# HDMI_to_RGB.net
KiCad netlist of a schematic drawn in Altium Designer
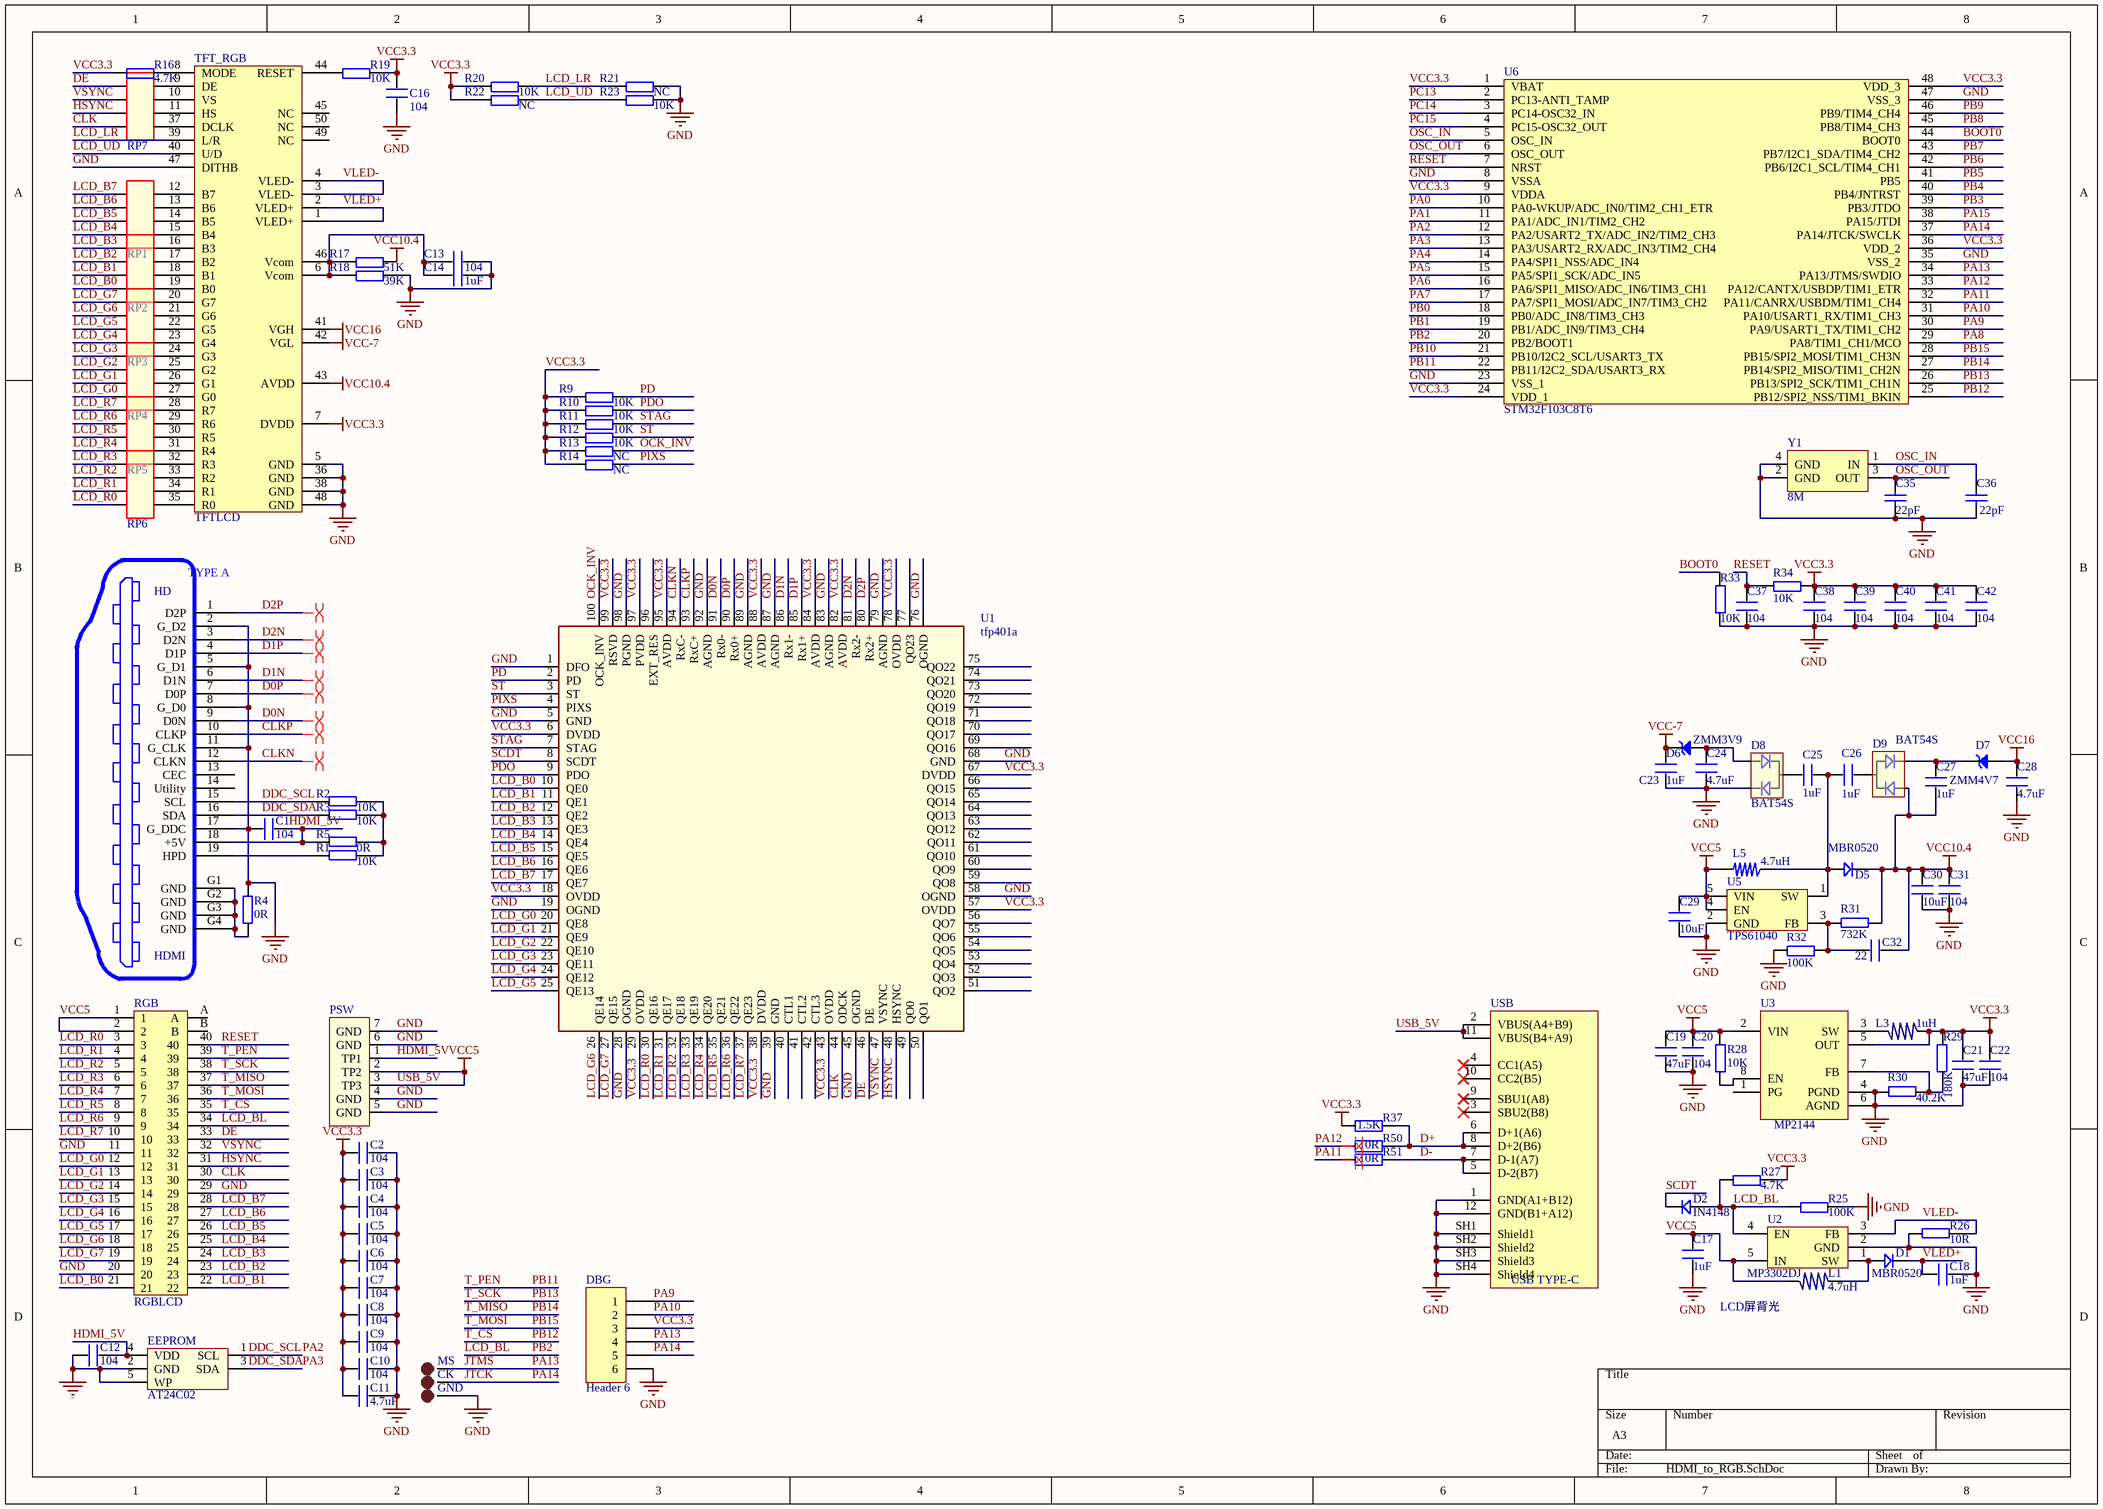
[diagram p0: HDMI_to_RGB.SchDoc]

(export (version "E")
  (design (tool "Eeschema 10.0.6"))
  (components
    (comp (ref "C1")
      (value "104")
      (footprint "C 0603_L")
      (libsource (lib "WarShip V3 STM32103封装库") (part "C"))
    )
    (comp (ref "C2")
      (value "104")
      (footprint "C 0603_L")
      (libsource (lib "WarShip V3 STM32103封装库") (part "C"))
    )
    (comp (ref "C3")
      (value "104")
      (footprint "C 0603_L")
      (libsource (lib "WarShip V3 STM32103封装库") (part "C"))
    )
    (comp (ref "C4")
      (value "104")
      (footprint "C 0603_L")
      (libsource (lib "WarShip V3 STM32103封装库") (part "C"))
    )
    (comp (ref "C5")
      (value "104")
      (footprint "C 0603_L")
      (libsource (lib "WarShip V3 STM32103封装库") (part "C"))
    )
    (comp (ref "C6")
      (value "104")
      (footprint "C 0603_L")
      (libsource (lib "WarShip V3 STM32103封装库") (part "C"))
    )
    (comp (ref "C7")
      (value "104")
      (footprint "C 0603_L")
      (libsource (lib "WarShip V3 STM32103封装库") (part "C"))
    )
    (comp (ref "C8")
      (value "104")
      (footprint "C 0603_L")
      (libsource (lib "WarShip V3 STM32103封装库") (part "C"))
    )
    (comp (ref "C9")
      (value "104")
      (footprint "C 0603_L")
      (libsource (lib "WarShip V3 STM32103封装库") (part "C"))
    )
    (comp (ref "C10")
      (value "104")
      (footprint "C 0603_L")
      (libsource (lib "WarShip V3 STM32103封装库") (part "C"))
    )
    (comp (ref "C11")
      (value "4.7uF")
      (footprint "C 0603_L")
      (libsource (lib "WarShip V3 STM32103封装库") (part "C"))
    )
    (comp (ref "C12")
      (value "104")
      (footprint "C 0603_L")
      (libsource (lib "WarShip V3 STM32103封装库") (part "C"))
    )
    (comp (ref "C13")
      (value "104")
      (footprint "C 0603_L")
      (libsource (lib "WarShip V3 STM32103封装库") (part "C"))
    )
    (comp (ref "C14")
      (value "1uF")
      (footprint "C 0603_L")
      (libsource (lib "WarShip V3 STM32103封装库") (part "C"))
    )
    (comp (ref "C16")
      (value "104")
      (footprint "C 0603_L")
      (libsource (lib "WarShip V3 STM32103封装库") (part "C"))
    )
    (comp (ref "C17") (value "1uF") (footprint "C 0603_L") (libsource (lib "阿波罗STM32F4&F7底板封装库") (part "C")))
    (comp (ref "C18") (value "1uF") (footprint "C 0603_L") (libsource (lib "阿波罗STM32F4&F7底板封装库") (part "C")))
    (comp (ref "C19")
      (value "47uF")
      (footprint "C 0805_L")
      (libsource (lib "WarShip V3 STM32103封装库") (part "C"))
    )
    (comp (ref "C20")
      (value "104")
      (footprint "C 0603_L")
      (libsource (lib "WarShip V3 STM32103封装库") (part "C"))
    )
    (comp (ref "C21")
      (value "47uF")
      (footprint "C 0805_L")
      (libsource (lib "WarShip V3 STM32103封装库") (part "C"))
    )
    (comp (ref "C22")
      (value "104")
      (footprint "C 0603_L")
      (libsource (lib "WarShip V3 STM32103封装库") (part "C"))
    )
    (comp (ref "C23") (value "1uF") (footprint "C 0603_L") (libsource (lib "ALIENTEK_COMPONENT") (part "C")))
    (comp (ref "C24")
      (value "4.7uF")
      (footprint "C 0603_L")
      (libsource (lib "ALIENTEK_COMPONENT") (part "C"))
    )
    (comp (ref "C25") (value "1uF") (footprint "C 0603_L") (libsource (lib "ALIENTEK_COMPONENT") (part "C")))
    (comp (ref "C26") (value "1uF") (footprint "C 0603_L") (libsource (lib "ALIENTEK_COMPONENT") (part "C")))
    (comp (ref "C27") (value "1uF") (footprint "C 0603_L") (libsource (lib "ALIENTEK_COMPONENT") (part "C")))
    (comp (ref "C28")
      (value "4.7uF")
      (footprint "C 0603_L")
      (libsource (lib "ALIENTEK_COMPONENT") (part "C"))
    )
    (comp (ref "C29") (value "10uF") (footprint "C 0603_L") (libsource (lib "ALIENTEK_COMPONENT") (part "C")))
    (comp (ref "C30") (value "10uF") (footprint "C 0603_L") (libsource (lib "ALIENTEK_COMPONENT") (part "C")))
    (comp (ref "C31") (value "104") (footprint "C 0603_L") (libsource (lib "ALIENTEK_COMPONENT") (part "C")))
    (comp (ref "C32") (value "22") (footprint "C 0603_L") (libsource (lib "ALIENTEK_COMPONENT") (part "C")))
    (comp (ref "C35") (value "22pF") (footprint "C 0603_L") (libsource (lib "L476") (part "CAP")))
    (comp (ref "C36") (value "22pF") (footprint "C 0603_L") (libsource (lib "L476") (part "CAP")))
    (comp (ref "C37")
      (value "104")
      (footprint "C 0603_L")
      (libsource (lib "WarShip V3 STM32103封装库") (part "C"))
    )
    (comp (ref "C38")
      (value "104")
      (footprint "C 0603_L")
      (libsource (lib "WarShip V3 STM32103封装库") (part "C"))
    )
    (comp (ref "C39")
      (value "104")
      (footprint "C 0603_L")
      (libsource (lib "WarShip V3 STM32103封装库") (part "C"))
    )
    (comp (ref "C40")
      (value "104")
      (footprint "C 0603_L")
      (libsource (lib "WarShip V3 STM32103封装库") (part "C"))
    )
    (comp (ref "C41")
      (value "104")
      (footprint "C 0603_L")
      (libsource (lib "WarShip V3 STM32103封装库") (part "C"))
    )
    (comp (ref "C42")
      (value "104")
      (footprint "C 0603_L")
      (libsource (lib "WarShip V3 STM32103封装库") (part "C"))
    )
    (comp (ref "CK")
      (value "TEST POINT")
      (footprint "TP-1.5")
      (description "测试点")
      (libsource (lib "STM32F767核心板封装库") (part "TEST-POINT"))
    )
    (comp (ref "D1")
      (value "MBR0520")
      (footprint "二极管-整流桥:SOD-123")
      (description "1N4148")
      (libsource (lib "ATK-4.3' TFTLCD电容触摸屏模块_V1.2") (part "D"))
    )
    (comp (ref "D2")
      (value "IN4148")
      (footprint "二极管-整流桥:SOD-123")
      (description "1N4148")
      (libsource (lib "ATK-4.3' TFTLCD电容触摸屏模块_V1.2") (part "D"))
    )
    (comp (ref "D5")
      (value "MBR0520")
      (footprint "二极管-整流桥:SOD-123")
      (description "1N4148")
      (libsource (lib "ALIENTEK_COMPONENT") (part "D"))
    )
    (comp (ref "D6")
      (value "ZMM3V9")
      (footprint "MINI_MELF (LL34)")
      (description "ZMM3V6")
      (libsource (lib "ALIENTEK_COMPONENT") (part "ZMM3V6"))
    )
    (comp (ref "D7")
      (value "ZMM4V7")
      (footprint "MINI_MELF (LL34)")
      (description "ZMM3V6")
      (libsource (lib "ALIENTEK_COMPONENT") (part "ZMM3V6"))
    )
    (comp (ref "D8")
      (value "BAT54S")
      (footprint "SOT23-3L")
      (description "双肖特基二极管")
      (libsource (lib "ALIENTEK_COMPONENT") (part "BAT54S"))
    )
    (comp (ref "D9")
      (value "BAT54S")
      (footprint "SOT23-3L")
      (description "双肖特基二极管")
      (libsource (lib "") (part "BAT54S_1"))
    )
    (comp (ref "DBG")
      (value "Header 6")
      (footprint "MX 1.25-LI-6P")
      (description "Header, 6-Pin")
      (fields (field (name "PUBLISHER") "Altium Limited"))
      (libsource (lib "Miscellaneous Connectors") (part "Header 6"))
    )
    (comp (ref "EEPROM")
      (value "AT24C02")
      (footprint "AT24C02")
      (libsource (lib "stm32f767igt6simple") (part "AT24C02"))
    )
    (comp (ref "GND")
      (value "TEST POINT")
      (footprint "TP-1.5")
      (description "测试点")
      (libsource (lib "STM32F767核心板封装库") (part "TEST-POINT"))
    )
    (comp (ref "HD")
      (value "HDMI")
      (footprint "HDMI_A")
      (libsource (lib "stm32f767igt6simple") (part "HDMI"))
    )
    (comp (ref "L1")
      (value "4.7uH")
      (footprint "NR4010")
      (libsource (lib "ATK-4.3' TFTLCD电容触摸屏模块_V1.2") (part "L"))
    )
    (comp (ref "L3") (value "1uH") (footprint "NR3015") (libsource (lib "MiniFly ") (part "L")))
    (comp (ref "L5")
      (value "4.7uH")
      (footprint "NR4010")
      (libsource (lib "ALIENTEK_COMPONENT") (part "L_SOP"))
    )
    (comp (ref "MS")
      (value "TEST POINT")
      (footprint "TP-1.5")
      (description "测试点")
      (libsource (lib "STM32F767核心板封装库") (part "TEST-POINT"))
    )
    (comp (ref "PSW") (value "SWITCH") (footprint "SWITCH") (libsource (lib "TP4056") (part "SWITCH")))
    (comp (ref "R1")
      (value "10K")
      (footprint "R 0603_L")
      (libsource (lib "WarShip V3 STM32103封装库") (part "R"))
    )
    (comp (ref "R2")
      (value "10K")
      (footprint "R 0603_L")
      (libsource (lib "WarShip V3 STM32103封装库") (part "R"))
    )
    (comp (ref "R3")
      (value "10K")
      (footprint "R 0603_L")
      (libsource (lib "WarShip V3 STM32103封装库") (part "R"))
    )
    (comp (ref "R4")
      (value "0R")
      (footprint "R 0603_L")
      (libsource (lib "WarShip V3 STM32103封装库") (part "R"))
    )
    (comp (ref "R5")
      (value "0R")
      (footprint "R 0603_L")
      (libsource (lib "WarShip V3 STM32103封装库") (part "R"))
    )
    (comp (ref "R9")
      (value "10K")
      (footprint "R 0603_L")
      (libsource (lib "WarShip V3 STM32103封装库") (part "R"))
    )
    (comp (ref "R10")
      (value "10K")
      (footprint "R 0603_L")
      (libsource (lib "WarShip V3 STM32103封装库") (part "R"))
    )
    (comp (ref "R11")
      (value "10K")
      (footprint "R 0603_L")
      (libsource (lib "WarShip V3 STM32103封装库") (part "R"))
    )
    (comp (ref "R12")
      (value "10K")
      (footprint "R 0603_L")
      (libsource (lib "WarShip V3 STM32103封装库") (part "R"))
    )
    (comp (ref "R13")
      (value "NC")
      (footprint "R 0603_L")
      (libsource (lib "WarShip V3 STM32103封装库") (part "R"))
    )
    (comp (ref "R14")
      (value "NC")
      (footprint "R 0603_L")
      (libsource (lib "WarShip V3 STM32103封装库") (part "R"))
    )
    (comp (ref "R16")
      (value "4.7K")
      (footprint "R 0603_L")
      (libsource (lib "WarShip V3 STM32103封装库") (part "R"))
    )
    (comp (ref "R17")
      (value "51K")
      (footprint "R 0603_L")
      (libsource (lib "WarShip V3 STM32103封装库") (part "R"))
    )
    (comp (ref "R18")
      (value "39K")
      (footprint "R 0603_L")
      (libsource (lib "WarShip V3 STM32103封装库") (part "R"))
    )
    (comp (ref "R19")
      (value "10K")
      (footprint "R 0603_L")
      (libsource (lib "WarShip V3 STM32103封装库") (part "R"))
    )
    (comp (ref "R20")
      (value "10K")
      (footprint "R 0603_L")
      (libsource (lib "WarShip V3 STM32103封装库") (part "R"))
    )
    (comp (ref "R21")
      (value "NC")
      (footprint "R 0603_L")
      (libsource (lib "WarShip V3 STM32103封装库") (part "R"))
    )
    (comp (ref "R22")
      (value "NC")
      (footprint "R 0603_L")
      (libsource (lib "WarShip V3 STM32103封装库") (part "R"))
    )
    (comp (ref "R23")
      (value "10K")
      (footprint "R 0603_L")
      (libsource (lib "WarShip V3 STM32103封装库") (part "R"))
    )
    (comp (ref "R25") (value "100K") (footprint "R 0603_L") (libsource (lib "阿波罗STM32F4&F7底板封装库") (part "R")))
    (comp (ref "R26") (value "10R") (footprint "R 0603_L") (libsource (lib "阿波罗STM32F4&F7底板封装库") (part "R")))
    (comp (ref "R27")
      (value "4.7K")
      (footprint "R 0603_L")
      (libsource (lib "WarShip V3 STM32103封装库") (part "R"))
    )
    (comp (ref "R28") (value "10K") (footprint "R 0603_L") (libsource (lib "阿波罗STM32F4&F7底板封装库") (part "R")))
    (comp (ref "R29") (value "180K") (footprint "R 0603_L") (libsource (lib "") (part "R_1")))
    (comp (ref "R30") (value "40.2K") (footprint "R 0603_L") (libsource (lib "") (part "R_1")))
    (comp (ref "R31") (value "732K") (footprint "R 0603_L") (libsource (lib "ALIENTEK_COMPONENT") (part "R")))
    (comp (ref "R32") (value "100K") (footprint "R 0603_L") (libsource (lib "ALIENTEK_COMPONENT") (part "R")))
    (comp (ref "R33")
      (value "10K")
      (footprint "R 0603_L")
      (libsource (lib "WarShip V3 STM32103封装库") (part "R"))
    )
    (comp (ref "R34")
      (value "10K")
      (footprint "R 0603_L")
      (libsource (lib "WarShip V3 STM32103封装库") (part "R"))
    )
    (comp (ref "R37")
      (value "1.5K")
      (footprint "R 0603_L")
      (description "贴片电阻")
      (fields (field (name "版权归属") "源创客"))
      (libsource (lib "电阻-电容-电感") (part "R"))
    )
    (comp (ref "R50")
      (value "10R")
      (footprint "R 0603_L")
      (description "贴片电阻")
      (fields (field (name "版权归属") "源创客"))
      (libsource (lib "电阻-电容-电感") (part "R"))
    )
    (comp (ref "R51")
      (value "10R")
      (footprint "R 0603_L")
      (description "贴片电阻")
      (fields (field (name "版权归属") "源创客"))
      (libsource (lib "电阻-电容-电感") (part "R"))
    )
    (comp (ref "RGB")
      (value "RGBLCD")
      (footprint "FPC0.5 2H-WS-40P")
      (description "FPC-40P-0.5mm")
      (libsource (lib "STM32F429核心板封装库") (part "FPC-40"))
    )
    (comp (ref "RP1")
      (value "33R")
      (footprint "P_pack")
      (libsource (lib "stm32f767igt6simple") (part "R_pack"))
    )
    (comp (ref "RP2")
      (value "33R")
      (footprint "P_pack")
      (libsource (lib "stm32f767igt6simple") (part "R_pack"))
    )
    (comp (ref "RP3")
      (value "33R")
      (footprint "P_pack")
      (libsource (lib "stm32f767igt6simple") (part "R_pack"))
    )
    (comp (ref "RP4")
      (value "33R")
      (footprint "P_pack")
      (libsource (lib "stm32f767igt6simple") (part "R_pack"))
    )
    (comp (ref "RP5")
      (value "33R")
      (footprint "P_pack")
      (libsource (lib "stm32f767igt6simple") (part "R_pack"))
    )
    (comp (ref "RP6")
      (value "33R")
      (footprint "P_pack")
      (libsource (lib "stm32f767igt6simple") (part "R_pack"))
    )
    (comp (ref "RP7")
      (value "33R")
      (footprint "P_pack")
      (libsource (lib "stm32f767igt6simple") (part "R_pack"))
    )
    (comp (ref "TFT_RGB")
      (value "TFTLCD")
      (footprint "FPC-TOP50")
      (description "7' TFTLCD")
      (libsource (lib "ATK-7016&7084 7寸RGB屏模块封装库") (part "AT070TN92"))
    )
    (comp (ref "U1")
      (value "tfp401a")
      (footprint "LQFP100")
      (libsource (lib "stm32f767igt6simple") (part "tfp401a"))
    )
    (comp (ref "U2")
      (value "MP3302DJ")
      (footprint "SOT:SOT23-5L")
      (description "LCD背光IC")
      (libsource (lib "ATK-4.3' TFTLCD电容触摸屏模块_V1.2") (part "MP3302"))
    )
    (comp (ref "U3") (value "MP2144") (footprint "SOT23-8L") (libsource (lib "LDO和DCDC") (part "MP2144")))
    (comp (ref "U5")
      (value "TPS61040")
      (footprint "SOT:SOT23-5L")
      (description "DC DC Step Up IC")
      (libsource (lib "ALIENTEK_COMPONENT") (part "TPS61040"))
    )
    (comp (ref "U6")
      (value "STM32F103C8T6")
      (footprint "LQFP48 7X7_L")
      (libsource (lib "Pandora_STM32L4_Board_V2.4") (part "U-STM32F103C8T6"))
    )
    (comp (ref "USB")
      (value "USB TypeC")
      (footprint "USB Type-C")
      (description "12P TypeC 母座")
      (libsource (lib "接口类") (part "USB Type-C"))
    )
    (comp (ref "Y1")
      (value "8M")
      (footprint "OSC 3225-4P")
      (description "4脚无源晶振")
      (fields (field (name "版权归属") "源创客"))
      (libsource (lib "保险丝-晶振") (part "XTAL-4P"))
    )
  )
  (nets
    (net (code "1") (name "/BOOT0") (class "Default")
      (node (ref "R33") (pin "2") (pintype "passive"))
      (node (ref "U6") (pin "44") (pinfunction "BOOT0_44") (pintype "passive"))
    )
    (net (code "2") (name "/CLK") (class "Default")
      (node (ref "RGB") (pin "30") (pinfunction "30_30") (pintype "passive"))
      (node (ref "RP7") (pin "7") (pintype "passive"))
      (node (ref "U1") (pin "44") (pinfunction "ODCK_44") (pintype "passive"))
    )
    (net (code "3") (name "/CLKN") (class "Default")
      (node (ref "HD") (pin "12") (pinfunction "CLKN_12") (pintype "passive"))
      (node (ref "U1") (pin "94") (pinfunction "RxC-_94") (pintype "passive"))
    )
    (net (code "4") (name "/CLKP") (class "Default")
      (node (ref "HD") (pin "10") (pinfunction "CLKP_10") (pintype "passive"))
      (node (ref "U1") (pin "93") (pinfunction "RxC+_93") (pintype "passive"))
    )
    (net (code "5") (name "/D+") (class "Default")
      (node (ref "R37") (pin "1") (pinfunction "1_1") (pintype "passive"))
      (node (ref "R50") (pin "1") (pinfunction "1_1") (pintype "passive"))
      (node (ref "USB") (pin "6") (pinfunction "D+1(A6)_6") (pintype "passive"))
      (node (ref "USB") (pin "8") (pinfunction "D+2(B6)_8") (pintype "passive"))
    )
    (net (code "6") (name "/D-") (class "Default")
      (node (ref "R51") (pin "1") (pinfunction "1_1") (pintype "passive"))
      (node (ref "USB") (pin "5") (pinfunction "D-2(B7)_5") (pintype "passive"))
      (node (ref "USB") (pin "7") (pinfunction "D-1(A7)_7") (pintype "passive"))
    )
    (net (code "7") (name "/D0N") (class "Default")
      (node (ref "HD") (pin "9") (pinfunction "D0N_9") (pintype "passive"))
      (node (ref "U1") (pin "91") (pinfunction "Rx0-_91") (pintype "passive"))
    )
    (net (code "8") (name "/D0P") (class "Default")
      (node (ref "HD") (pin "7") (pinfunction "D0P_7") (pintype "passive"))
      (node (ref "U1") (pin "90") (pinfunction "Rx0+_90") (pintype "passive"))
    )
    (net (code "9") (name "/D1N") (class "Default")
      (node (ref "HD") (pin "6") (pinfunction "D1N_6") (pintype "passive"))
      (node (ref "U1") (pin "86") (pinfunction "Rx1-_86") (pintype "passive"))
    )
    (net (code "10") (name "/D1P") (class "Default")
      (node (ref "HD") (pin "4") (pinfunction "D1P_4") (pintype "passive"))
      (node (ref "U1") (pin "85") (pinfunction "Rx1+_85") (pintype "passive"))
    )
    (net (code "11") (name "/D2N") (class "Default")
      (node (ref "HD") (pin "3") (pinfunction "D2N_3") (pintype "passive"))
      (node (ref "U1") (pin "81") (pinfunction "Rx2-_81") (pintype "passive"))
    )
    (net (code "12") (name "/D2P") (class "Default")
      (node (ref "HD") (pin "1") (pinfunction "D2P_1") (pintype "passive"))
      (node (ref "U1") (pin "80") (pinfunction "Rx2+_80") (pintype "passive"))
    )
    (net (code "13") (name "/DDC_SCL") (class "Default")
      (node (ref "EEPROM") (pin "1") (pinfunction "SCL_1") (pintype "passive"))
      (node (ref "HD") (pin "15") (pinfunction "SCL_15") (pintype "passive"))
      (node (ref "R2") (pin "2") (pintype "passive"))
      (node (ref "U6") (pin "12") (pinfunction "PA2/USART2_TX/ADC_IN2/TIM2_CH3_12") (pintype "passive"))
    )
    (net (code "14") (name "/DDC_SDA") (class "Default")
      (node (ref "EEPROM") (pin "3") (pinfunction "SDA_3") (pintype "passive"))
      (node (ref "HD") (pin "16") (pinfunction "SDA_16") (pintype "passive"))
      (node (ref "R3") (pin "2") (pintype "passive"))
      (node (ref "U6") (pin "13") (pinfunction "PA3/USART2_RX/ADC_IN3/TIM2_CH4_13") (pintype "passive"))
    )
    (net (code "15") (name "/DE") (class "Default")
      (node (ref "RGB") (pin "33") (pinfunction "33_33") (pintype "passive"))
      (node (ref "RP7") (pin "1") (pinfunction "1_1") (pintype "passive"))
      (node (ref "U1") (pin "46") (pinfunction "DE_46") (pintype "passive"))
    )
    (net (code "16") (name "/HDMI_5V") (class "Default")
      (node (ref "C1") (pin "1") (pintype "passive"))
      (node (ref "C12") (pin "2") (pintype "passive"))
      (node (ref "EEPROM") (pin "4") (pinfunction "VDD_4") (pintype "passive"))
      (node (ref "HD") (pin "18") (pinfunction "+5V_18") (pintype "passive"))
      (node (ref "PSW") (pin "1") (pinfunction "TP1_1") (pintype "passive"))
      (node (ref "R5") (pin "2") (pintype "passive"))
    )
    (net (code "17") (name "/HSYNC") (class "Default")
      (node (ref "RGB") (pin "31") (pinfunction "31_31") (pintype "passive"))
      (node (ref "RP7") (pin "5") (pintype "passive"))
      (node (ref "U1") (pin "48") (pinfunction "HSYNC_48") (pintype "passive"))
    )
    (net (code "18") (name "/JTCK") (class "Default")
      (node (ref "CK") (pin "1") (pinfunction "1_1") (pintype "passive"))
      (node (ref "DBG") (pin "5") (pinfunction "5_5") (pintype "passive"))
      (node (ref "U6") (pin "37") (pinfunction "PA14/JTCK/SWCLK_37") (pintype "passive"))
    )
    (net (code "19") (name "/JTMS") (class "Default")
      (node (ref "DBG") (pin "4") (pinfunction "4_4") (pintype "passive"))
      (node (ref "MS") (pin "1") (pinfunction "1_1") (pintype "passive"))
      (node (ref "U6") (pin "34") (pinfunction "PA13/JTMS/SWDIO_34") (pintype "passive"))
    )
    (net (code "20") (name "/LCD_B0") (class "Default")
      (node (ref "RGB") (pin "21") (pinfunction "21_21") (pintype "passive"))
      (node (ref "RP2") (pin "7") (pintype "passive"))
      (node (ref "U1") (pin "10") (pinfunction "QE0_10") (pintype "passive"))
    )
    (net (code "21") (name "/LCD_B1") (class "Default")
      (node (ref "RGB") (pin "22") (pinfunction "22_22") (pintype "passive"))
      (node (ref "RP2") (pin "5") (pintype "passive"))
      (node (ref "U1") (pin "11") (pinfunction "QE1_11") (pintype "passive"))
    )
    (net (code "22") (name "/LCD_B2") (class "Default")
      (node (ref "RGB") (pin "23") (pinfunction "23_23") (pintype "passive"))
      (node (ref "RP2") (pin "3") (pintype "passive"))
      (node (ref "U1") (pin "12") (pinfunction "QE2_12") (pintype "passive"))
    )
    (net (code "23") (name "/LCD_B3") (class "Default")
      (node (ref "RGB") (pin "24") (pinfunction "24_24") (pintype "passive"))
      (node (ref "RP2") (pin "1") (pinfunction "1_1") (pintype "passive"))
      (node (ref "U1") (pin "13") (pinfunction "QE3_13") (pintype "passive"))
    )
    (net (code "24") (name "/LCD_B4") (class "Default")
      (node (ref "RGB") (pin "25") (pinfunction "25_25") (pintype "passive"))
      (node (ref "RP1") (pin "7") (pintype "passive"))
      (node (ref "U1") (pin "14") (pinfunction "QE4_14") (pintype "passive"))
    )
    (net (code "25") (name "/LCD_B5") (class "Default")
      (node (ref "RGB") (pin "26") (pinfunction "26_26") (pintype "passive"))
      (node (ref "RP1") (pin "5") (pintype "passive"))
      (node (ref "U1") (pin "15") (pinfunction "QE5_15") (pintype "passive"))
    )
    (net (code "26") (name "/LCD_B6") (class "Default")
      (node (ref "RGB") (pin "27") (pinfunction "27_27") (pintype "passive"))
      (node (ref "RP1") (pin "3") (pintype "passive"))
      (node (ref "U1") (pin "16") (pinfunction "QE6_16") (pintype "passive"))
    )
    (net (code "27") (name "/LCD_B7") (class "Default")
      (node (ref "RGB") (pin "28") (pinfunction "28_28") (pintype "passive"))
      (node (ref "RP1") (pin "1") (pinfunction "1_1") (pintype "passive"))
      (node (ref "U1") (pin "17") (pinfunction "QE7_17") (pintype "passive"))
    )
    (net (code "28") (name "/LCD_BL") (class "Default")
      (node (ref "D2") (pin "1") (pintype "passive"))
      (node (ref "R25") (pin "1") (pintype "passive"))
      (node (ref "R27") (pin "1") (pintype "passive"))
      (node (ref "RGB") (pin "34") (pinfunction "34_34") (pintype "passive"))
      (node (ref "U2") (pin "4") (pinfunction "EN_4") (pintype "passive"))
      (node (ref "U6") (pin "20") (pinfunction "PB2/BOOT1_20") (pintype "passive"))
    )
    (net (code "29") (name "/LCD_G0") (class "Default")
      (node (ref "RGB") (pin "12") (pinfunction "12_12") (pintype "passive"))
      (node (ref "RP4") (pin "7") (pintype "passive"))
      (node (ref "U1") (pin "20") (pinfunction "QE8_20") (pintype "passive"))
    )
    (net (code "30") (name "/LCD_G1") (class "Default")
      (node (ref "RGB") (pin "13") (pinfunction "13_13") (pintype "passive"))
      (node (ref "RP4") (pin "5") (pintype "passive"))
      (node (ref "U1") (pin "21") (pinfunction "QE9_21") (pintype "passive"))
    )
    (net (code "31") (name "/LCD_G2") (class "Default")
      (node (ref "RGB") (pin "14") (pinfunction "14_14") (pintype "passive"))
      (node (ref "RP4") (pin "3") (pintype "passive"))
      (node (ref "U1") (pin "22") (pinfunction "QE10_22") (pintype "passive"))
    )
    (net (code "32") (name "/LCD_G3") (class "Default")
      (node (ref "RGB") (pin "15") (pinfunction "15_15") (pintype "passive"))
      (node (ref "RP4") (pin "1") (pinfunction "1_1") (pintype "passive"))
      (node (ref "U1") (pin "23") (pinfunction "QE11_23") (pintype "passive"))
    )
    (net (code "33") (name "/LCD_G4") (class "Default")
      (node (ref "RGB") (pin "16") (pinfunction "16_16") (pintype "passive"))
      (node (ref "RP3") (pin "7") (pintype "passive"))
      (node (ref "U1") (pin "24") (pinfunction "QE12_24") (pintype "passive"))
    )
    (net (code "34") (name "/LCD_G5") (class "Default")
      (node (ref "RGB") (pin "17") (pinfunction "17_17") (pintype "passive"))
      (node (ref "RP3") (pin "5") (pintype "passive"))
      (node (ref "U1") (pin "25") (pinfunction "QE13_25") (pintype "passive"))
    )
    (net (code "35") (name "/LCD_G6") (class "Default")
      (node (ref "RGB") (pin "18") (pinfunction "18_18") (pintype "passive"))
      (node (ref "RP3") (pin "3") (pintype "passive"))
      (node (ref "U1") (pin "26") (pinfunction "QE14_26") (pintype "passive"))
    )
    (net (code "36") (name "/LCD_G7") (class "Default")
      (node (ref "RGB") (pin "19") (pinfunction "19_19") (pintype "passive"))
      (node (ref "RP3") (pin "1") (pinfunction "1_1") (pintype "passive"))
      (node (ref "U1") (pin "27") (pinfunction "QE15_27") (pintype "passive"))
    )
    (net (code "37") (name "/LCD_LR") (class "Default")
      (node (ref "R20") (pin "2") (pintype "passive"))
      (node (ref "R21") (pin "1") (pintype "passive"))
      (node (ref "TFT_RGB") (pin "39") (pinfunction "L/R_39") (pintype "passive"))
    )
    (net (code "38") (name "/LCD_R0") (class "Default")
      (node (ref "RGB") (pin "3") (pinfunction "3_3") (pintype "passive"))
      (node (ref "RP6") (pin "7") (pintype "passive"))
      (node (ref "U1") (pin "30") (pinfunction "QE16_30") (pintype "passive"))
    )
    (net (code "39") (name "/LCD_R1") (class "Default")
      (node (ref "RGB") (pin "4") (pinfunction "4_4") (pintype "passive"))
      (node (ref "RP6") (pin "5") (pintype "passive"))
      (node (ref "U1") (pin "31") (pinfunction "QE17_31") (pintype "passive"))
    )
    (net (code "40") (name "/LCD_R2") (class "Default")
      (node (ref "RGB") (pin "5") (pinfunction "5_5") (pintype "passive"))
      (node (ref "RP6") (pin "3") (pintype "passive"))
      (node (ref "U1") (pin "32") (pinfunction "QE18_32") (pintype "passive"))
    )
    (net (code "41") (name "/LCD_R3") (class "Default")
      (node (ref "RGB") (pin "6") (pinfunction "6_6") (pintype "passive"))
      (node (ref "RP6") (pin "1") (pinfunction "1_1") (pintype "passive"))
      (node (ref "U1") (pin "33") (pinfunction "QE19_33") (pintype "passive"))
    )
    (net (code "42") (name "/LCD_R4") (class "Default")
      (node (ref "RGB") (pin "7") (pinfunction "7_7") (pintype "passive"))
      (node (ref "RP5") (pin "7") (pintype "passive"))
      (node (ref "U1") (pin "34") (pinfunction "QE20_34") (pintype "passive"))
    )
    (net (code "43") (name "/LCD_R5") (class "Default")
      (node (ref "RGB") (pin "8") (pinfunction "8_8") (pintype "passive"))
      (node (ref "RP5") (pin "5") (pintype "passive"))
      (node (ref "U1") (pin "35") (pinfunction "QE21_35") (pintype "passive"))
    )
    (net (code "44") (name "/LCD_R6") (class "Default")
      (node (ref "RGB") (pin "9") (pinfunction "9_9") (pintype "passive"))
      (node (ref "RP5") (pin "3") (pintype "passive"))
      (node (ref "U1") (pin "36") (pinfunction "QE22_36") (pintype "passive"))
    )
    (net (code "45") (name "/LCD_R7") (class "Default")
      (node (ref "RGB") (pin "10") (pinfunction "10_10") (pintype "passive"))
      (node (ref "RP5") (pin "1") (pinfunction "1_1") (pintype "passive"))
      (node (ref "U1") (pin "37") (pinfunction "QE23_37") (pintype "passive"))
    )
    (net (code "46") (name "/LCD_UD") (class "Default")
      (node (ref "R22") (pin "2") (pintype "passive"))
      (node (ref "R23") (pin "1") (pintype "passive"))
      (node (ref "TFT_RGB") (pin "40") (pinfunction "U/D_40") (pintype "passive"))
    )
    (net (code "47") (name "/OCK_INV") (class "Default")
      (node (ref "R13") (pin "2") (pintype "passive"))
      (node (ref "U1") (pin "100") (pinfunction "OCK_INV_100") (pintype "passive"))
    )
    (net (code "48") (name "/OSC_IN") (class "Default")
      (node (ref "C36") (pin "2") (pinfunction "2_2") (pintype "passive"))
      (node (ref "U6") (pin "5") (pinfunction "OSC_IN_5") (pintype "passive"))
      (node (ref "Y1") (pin "1") (pinfunction "IN_1") (pintype "passive"))
    )
    (net (code "49") (name "/OSC_OUT") (class "Default")
      (node (ref "C35") (pin "2") (pinfunction "2_2") (pintype "passive"))
      (node (ref "U6") (pin "6") (pinfunction "OSC_OUT_6") (pintype "passive"))
      (node (ref "Y1") (pin "3") (pinfunction "OUT_3") (pintype "passive"))
    )
    (net (code "50") (name "/PA0") (class "Default")
      (node (ref "U6") (pin "10") (pinfunction "PA0-WKUP/ADC_IN0/TIM2_CH1_ETR_10") (pintype "passive"))
    )
    (net (code "51") (name "/PA1") (class "Default")
      (node (ref "U6") (pin "11") (pinfunction "PA1/ADC_IN1/TIM2_CH2_11") (pintype "passive"))
    )
    (net (code "52") (name "/PA4") (class "Default")
      (node (ref "U6") (pin "14") (pinfunction "PA4/SPI1_NSS/ADC_IN4_14") (pintype "passive"))
    )
    (net (code "53") (name "/PA5") (class "Default")
      (node (ref "U6") (pin "15") (pinfunction "PA5/SPI1_SCK/ADC_IN5_15") (pintype "passive"))
    )
    (net (code "54") (name "/PA6") (class "Default")
      (node (ref "U6") (pin "16") (pinfunction "PA6/SPI1_MISO/ADC_IN6/TIM3_CH1_16") (pintype "passive"))
    )
    (net (code "55") (name "/PA7") (class "Default")
      (node (ref "U6") (pin "17") (pinfunction "PA7/SPI1_MOSI/ADC_IN7/TIM3_CH2_17") (pintype "passive"))
    )
    (net (code "56") (name "/PA8") (class "Default")
      (node (ref "U6") (pin "29") (pinfunction "PA8/TIM1_CH1/MCO_29") (pintype "passive"))
    )
    (net (code "57") (name "/PA9") (class "Default")
      (node (ref "DBG") (pin "1") (pinfunction "1_1") (pintype "passive"))
      (node (ref "U6") (pin "30") (pinfunction "PA9/USART1_TX/TIM1_CH2_30") (pintype "passive"))
    )
    (net (code "58") (name "/PA10") (class "Default")
      (node (ref "DBG") (pin "2") (pinfunction "2_2") (pintype "passive"))
      (node (ref "U6") (pin "31") (pinfunction "PA10/USART1_RX/TIM1_CH3_31") (pintype "passive"))
    )
    (net (code "59") (name "/PA11") (class "Default")
      (node (ref "R51") (pin "2") (pinfunction "2_2") (pintype "passive"))
      (node (ref "U6") (pin "32") (pinfunction "PA11/CANRX/USBDM/TIM1_CH4_32") (pintype "passive"))
    )
    (net (code "60") (name "/PA12") (class "Default")
      (node (ref "R50") (pin "2") (pinfunction "2_2") (pintype "passive"))
      (node (ref "U6") (pin "33") (pinfunction "PA12/CANTX/USBDP/TIM1_ETR_33") (pintype "passive"))
    )
    (net (code "61") (name "/PA15") (class "Default")
      (node (ref "U6") (pin "38") (pinfunction "PA15/JTDI_38") (pintype "passive"))
    )
    (net (code "62") (name "/PB0") (class "Default")
      (node (ref "U6") (pin "18") (pinfunction "PB0/ADC_IN8/TIM3_CH3_18") (pintype "passive"))
    )
    (net (code "63") (name "/PB1") (class "Default")
      (node (ref "U6") (pin "19") (pinfunction "PB1/ADC_IN9/TIM3_CH4_19") (pintype "passive"))
    )
    (net (code "64") (name "/PB3") (class "Default")
      (node (ref "U6") (pin "39") (pinfunction "PB3/JTDO_39") (pintype "passive"))
    )
    (net (code "65") (name "/PB4") (class "Default")
      (node (ref "U6") (pin "40") (pinfunction "PB4/JNTRST_40") (pintype "passive"))
    )
    (net (code "66") (name "/PB5") (class "Default")
      (node (ref "U6") (pin "41") (pinfunction "PB5_41") (pintype "passive"))
    )
    (net (code "67") (name "/PB6") (class "Default")
      (node (ref "U6") (pin "42") (pinfunction "PB6/I2C1_SCL/TIM4_CH1_42") (pintype "passive"))
    )
    (net (code "68") (name "/PB7") (class "Default")
      (node (ref "U6") (pin "43") (pinfunction "PB7/I2C1_SDA/TIM4_CH2_43") (pintype "passive"))
    )
    (net (code "69") (name "/PB8") (class "Default")
      (node (ref "U6") (pin "45") (pinfunction "PB8/TIM4_CH3_45") (pintype "passive"))
    )
    (net (code "70") (name "/PB9") (class "Default")
      (node (ref "U6") (pin "46") (pinfunction "PB9/TIM4_CH4_46") (pintype "passive"))
    )
    (net (code "71") (name "/PB10") (class "Default")
      (node (ref "U6") (pin "21") (pinfunction "PB10/I2C2_SCL/USART3_TX_21") (pintype "passive"))
    )
    (net (code "72") (name "/PB11") (class "Default")
      (node (ref "RGB") (pin "39") (pinfunction "39_39") (pintype "passive"))
      (node (ref "U6") (pin "22") (pinfunction "PB11/I2C2_SDA/USART3_RX_22") (pintype "passive"))
    )
    (net (code "73") (name "/PB12") (class "Default")
      (node (ref "RGB") (pin "35") (pinfunction "35_35") (pintype "passive"))
      (node (ref "U6") (pin "25") (pinfunction "PB12/SPI2_NSS/TIM1_BKIN_25") (pintype "passive"))
    )
    (net (code "74") (name "/PB13") (class "Default")
      (node (ref "RGB") (pin "38") (pinfunction "38_38") (pintype "passive"))
      (node (ref "U6") (pin "26") (pinfunction "PB13/SPI2_SCK/TIM1_CH1N_26") (pintype "passive"))
    )
    (net (code "75") (name "/PB14") (class "Default")
      (node (ref "RGB") (pin "37") (pinfunction "37_37") (pintype "passive"))
      (node (ref "U6") (pin "27") (pinfunction "PB14/SPI2_MISO/TIM1_CH2N_27") (pintype "passive"))
    )
    (net (code "76") (name "/PB15") (class "Default")
      (node (ref "RGB") (pin "36") (pinfunction "36_36") (pintype "passive"))
      (node (ref "U6") (pin "28") (pinfunction "PB15/SPI2_MOSI/TIM1_CH3N_28") (pintype "passive"))
    )
    (net (code "77") (name "/PC13") (class "Default")
      (node (ref "U6") (pin "2") (pinfunction "PC13-ANTI_TAMP_2") (pintype "passive"))
    )
    (net (code "78") (name "/PC14") (class "Default")
      (node (ref "U6") (pin "3") (pinfunction "PC14-OSC32_IN_3") (pintype "passive"))
    )
    (net (code "79") (name "/PC15") (class "Default")
      (node (ref "U6") (pin "4") (pinfunction "PC15-OSC32_OUT_4") (pintype "passive"))
    )
    (net (code "80") (name "/PD") (class "Default")
      (node (ref "R9") (pin "2") (pintype "passive"))
      (node (ref "U1") (pin "2") (pinfunction "PD_2") (pintype "passive"))
    )
    (net (code "81") (name "/PDO") (class "Default")
      (node (ref "R10") (pin "2") (pintype "passive"))
      (node (ref "U1") (pin "9") (pinfunction "PDO_9") (pintype "passive"))
    )
    (net (code "82") (name "/PIXS") (class "Default")
      (node (ref "R14") (pin "2") (pintype "passive"))
      (node (ref "U1") (pin "4") (pinfunction "PIXS_4") (pintype "passive"))
    )
    (net (code "83") (name "/RESET") (class "Default")
      (node (ref "C37") (pin "2") (pintype "passive"))
      (node (ref "R34") (pin "1") (pintype "passive"))
      (node (ref "RGB") (pin "40") (pinfunction "40_40") (pintype "passive"))
      (node (ref "U6") (pin "7") (pinfunction "NRST_7") (pintype "passive"))
    )
    (net (code "84") (name "/SCDT") (class "Default")
      (node (ref "D2") (pin "2") (pintype "passive"))
      (node (ref "U1") (pin "8") (pinfunction "SCDT_8") (pintype "passive"))
    )
    (net (code "85") (name "/ST") (class "Default")
      (node (ref "R12") (pin "2") (pintype "passive"))
      (node (ref "U1") (pin "3") (pinfunction "ST_3") (pintype "passive"))
    )
    (net (code "86") (name "/STAG") (class "Default")
      (node (ref "R11") (pin "2") (pintype "passive"))
      (node (ref "U1") (pin "7") (pinfunction "STAG_7") (pintype "passive"))
    )
    (net (code "87") (name "/VLED+") (class "Default")
      (node (ref "C18") (pin "2") (pintype "passive"))
      (node (ref "D1") (pin "2") (pintype "passive"))
      (node (ref "TFT_RGB") (pin "1") (pinfunction "VLED+_1") (pintype "passive"))
      (node (ref "TFT_RGB") (pin "2") (pinfunction "VLED+_2") (pintype "passive"))
    )
    (net (code "88") (name "/VLED-") (class "Default")
      (node (ref "R26") (pin "1") (pintype "passive"))
      (node (ref "TFT_RGB") (pin "3") (pinfunction "VLED-_3") (pintype "passive"))
      (node (ref "TFT_RGB") (pin "4") (pinfunction "VLED-_4") (pintype "passive"))
      (node (ref "U2") (pin "3") (pinfunction "FB_3") (pintype "passive"))
    )
    (net (code "89") (name "/VSYNC") (class "Default")
      (node (ref "RGB") (pin "32") (pinfunction "32_32") (pintype "passive"))
      (node (ref "RP7") (pin "3") (pintype "passive"))
      (node (ref "U1") (pin "47") (pinfunction "VSYNC_47") (pintype "passive"))
    )
    (net (code "90") (name "GND") (class "Default")
      (node (ref "C1") (pin "2") (pintype "passive"))
      (node (ref "C10") (pin "1") (pintype "passive"))
      (node (ref "C11") (pin "1") (pintype "passive"))
      (node (ref "C12") (pin "1") (pintype "passive"))
      (node (ref "C13") (pin "2") (pintype "passive"))
      (node (ref "C14") (pin "2") (pintype "passive"))
      (node (ref "C16") (pin "1") (pintype "passive"))
      (node (ref "C17") (pin "1") (pintype "passive"))
      (node (ref "C18") (pin "1") (pintype "passive"))
      (node (ref "C19") (pin "1") (pintype "passive"))
      (node (ref "C2") (pin "1") (pintype "passive"))
      (node (ref "C20") (pin "1") (pintype "passive"))
      (node (ref "C21") (pin "1") (pintype "passive"))
      (node (ref "C22") (pin "1") (pintype "passive"))
      (node (ref "C23") (pin "2") (pintype "passive"))
      (node (ref "C24") (pin "2") (pintype "passive"))
      (node (ref "C28") (pin "1") (pintype "passive"))
      (node (ref "C29") (pin "1") (pintype "passive"))
      (node (ref "C3") (pin "1") (pintype "passive"))
      (node (ref "C30") (pin "1") (pintype "passive"))
      (node (ref "C31") (pin "2") (pintype "passive"))
      (node (ref "C35") (pin "1") (pinfunction "1_1") (pintype "passive"))
      (node (ref "C36") (pin "1") (pinfunction "1_1") (pintype "passive"))
      (node (ref "C37") (pin "1") (pintype "passive"))
      (node (ref "C38") (pin "1") (pintype "passive"))
      (node (ref "C39") (pin "1") (pintype "passive"))
      (node (ref "C4") (pin "1") (pintype "passive"))
      (node (ref "C40") (pin "1") (pintype "passive"))
      (node (ref "C41") (pin "1") (pintype "passive"))
      (node (ref "C42") (pin "1") (pintype "passive"))
      (node (ref "C5") (pin "1") (pintype "passive"))
      (node (ref "C6") (pin "1") (pintype "passive"))
      (node (ref "C7") (pin "1") (pintype "passive"))
      (node (ref "C8") (pin "1") (pintype "passive"))
      (node (ref "C9") (pin "1") (pintype "passive"))
      (node (ref "D8") (pin "2") (pintype "passive"))
      (node (ref "DBG") (pin "6") (pinfunction "6_6") (pintype "passive"))
      (node (ref "EEPROM") (pin "2") (pinfunction "GND_2") (pintype "passive"))
      (node (ref "EEPROM") (pin "5") (pinfunction "WP_5") (pintype "passive"))
      (node (ref "GND") (pin "1") (pinfunction "1_1") (pintype "passive"))
      (node (ref "HD") (pin "11") (pinfunction "G_CLK_11") (pintype "passive"))
      (node (ref "HD") (pin "17") (pinfunction "G_DDC_17") (pintype "passive"))
      (node (ref "HD") (pin "2") (pinfunction "G_D2_2") (pintype "passive"))
      (node (ref "HD") (pin "5") (pinfunction "G_D1_5") (pintype "passive"))
      (node (ref "HD") (pin "8") (pinfunction "G_D0_8") (pintype "passive"))
      (node (ref "PSW") (pin "4") (pinfunction "GND_4") (pintype "passive"))
      (node (ref "PSW") (pin "5") (pinfunction "GND_5") (pintype "passive"))
      (node (ref "PSW") (pin "6") (pinfunction "GND_6") (pintype "passive"))
      (node (ref "PSW") (pin "7") (pinfunction "GND_7") (pintype "passive"))
      (node (ref "R18") (pin "2") (pintype "passive"))
      (node (ref "R21") (pin "2") (pintype "passive"))
      (node (ref "R23") (pin "2") (pintype "passive"))
      (node (ref "R25") (pin "2") (pintype "passive"))
      (node (ref "R26") (pin "2") (pintype "passive"))
      (node (ref "R30") (pin "2") (pintype "passive"))
      (node (ref "R32") (pin "1") (pintype "passive"))
      (node (ref "R33") (pin "1") (pintype "passive"))
      (node (ref "R4") (pin "1") (pintype "passive"))
      (node (ref "RGB") (pin "11") (pinfunction "11_11") (pintype "passive"))
      (node (ref "RGB") (pin "20") (pinfunction "20_20") (pintype "passive"))
      (node (ref "RGB") (pin "29") (pinfunction "29_29") (pintype "passive"))
      (node (ref "TFT_RGB") (pin "36") (pinfunction "GND_36") (pintype "passive"))
      (node (ref "TFT_RGB") (pin "38") (pinfunction "GND_38") (pintype "passive"))
      (node (ref "TFT_RGB") (pin "47") (pinfunction "DITHB_47") (pintype "passive"))
      (node (ref "TFT_RGB") (pin "48") (pinfunction "GND_48") (pintype "passive"))
      (node (ref "TFT_RGB") (pin "5") (pinfunction "GND_5") (pintype "passive"))
      (node (ref "U1") (pin "1") (pinfunction "DFO_1") (pintype "passive"))
      (node (ref "U1") (pin "19") (pinfunction "OGND_19") (pintype "passive"))
      (node (ref "U1") (pin "28") (pinfunction "OGND_28") (pintype "passive"))
      (node (ref "U1") (pin "39") (pinfunction "GND_39") (pintype "passive"))
      (node (ref "U1") (pin "45") (pinfunction "OGND_45") (pintype "passive"))
      (node (ref "U1") (pin "5") (pinfunction "GND_5") (pintype "passive"))
      (node (ref "U1") (pin "58") (pinfunction "OGND_58") (pintype "passive"))
      (node (ref "U1") (pin "68") (pinfunction "GND_68") (pintype "passive"))
      (node (ref "U1") (pin "76") (pinfunction "OGND_76") (pintype "passive"))
      (node (ref "U1") (pin "79") (pinfunction "AGND_79") (pintype "passive"))
      (node (ref "U1") (pin "83") (pinfunction "AGND_83") (pintype "passive"))
      (node (ref "U1") (pin "87") (pinfunction "AGND_87") (pintype "passive"))
      (node (ref "U1") (pin "89") (pinfunction "AGND_89") (pintype "passive"))
      (node (ref "U1") (pin "92") (pinfunction "AGND_92") (pintype "passive"))
      (node (ref "U1") (pin "98") (pinfunction "PGND_98") (pintype "passive"))
      (node (ref "U2") (pin "2") (pinfunction "GND_2") (pintype "passive"))
      (node (ref "U3") (pin "4") (pinfunction "PGND_4") (pintype "passive"))
      (node (ref "U3") (pin "6") (pinfunction "AGND_6") (pintype "passive"))
      (node (ref "U5") (pin "2") (pinfunction "GND_2") (pintype "passive"))
      (node (ref "U6") (pin "23") (pinfunction "VSS_1_23") (pintype "passive"))
      (node (ref "U6") (pin "35") (pinfunction "VSS_2_35") (pintype "passive"))
      (node (ref "U6") (pin "47") (pinfunction "VSS_3_47") (pintype "passive"))
      (node (ref "U6") (pin "8") (pinfunction "VSSA_8") (pintype "passive"))
      (node (ref "USB") (pin "1") (pinfunction "GND(A1+B12)_1") (pintype "passive"))
      (node (ref "USB") (pin "12") (pinfunction "GND(B1+A12)_12") (pintype "passive"))
      (node (ref "USB") (pin "SH1") (pinfunction "Shield1_SH1") (pintype "passive"))
      (node (ref "USB") (pin "SH2") (pinfunction "Shield2_SH2") (pintype "passive"))
      (node (ref "USB") (pin "SH3") (pinfunction "Shield3_SH3") (pintype "passive"))
      (node (ref "USB") (pin "SH4") (pinfunction "Shield4_SH4") (pintype "passive"))
      (node (ref "Y1") (pin "2") (pinfunction "GND_2") (pintype "passive"))
      (node (ref "Y1") (pin "4") (pinfunction "GND_4") (pintype "passive"))
    )
    (net (code "91") (name "Net-(C13-Pad1)") (class "Default")
      (node (ref "C13") (pin "1") (pintype "passive"))
      (node (ref "C14") (pin "1") (pintype "passive"))
      (node (ref "R17") (pin "1") (pintype "passive"))
      (node (ref "R18") (pin "1") (pintype "passive"))
      (node (ref "TFT_RGB") (pin "46") (pinfunction "Vcom_46") (pintype "passive"))
      (node (ref "TFT_RGB") (pin "6") (pinfunction "Vcom_6") (pintype "passive"))
    )
    (net (code "92") (name "Net-(C24-Pad1)") (class "Default")
      (node (ref "C24") (pin "1") (pintype "passive"))
      (node (ref "D6") (pin "1") (pintype "passive"))
      (node (ref "D8") (pin "1") (pintype "passive"))
    )
    (net (code "93") (name "Net-(C25-Pad1)") (class "Default")
      (node (ref "C25") (pin "1") (pintype "passive"))
      (node (ref "D8") (pin "3") (pintype "passive"))
    )
    (net (code "94") (name "Net-(C26-Pad2)") (class "Default")
      (node (ref "C26") (pin "2") (pintype "passive"))
      (node (ref "D9") (pin "3") (pintype "passive"))
    )
    (net (code "95") (name "Net-(C27-Pad2)") (class "Default")
      (node (ref "C27") (pin "2") (pintype "passive"))
      (node (ref "D7") (pin "2") (pintype "passive"))
      (node (ref "D9") (pin "2") (pintype "passive"))
    )
    (net (code "96") (name "Net-(HD-GND-PadG1)") (class "Default")
      (node (ref "HD") (pin "G1") (pinfunction "GND_G1") (pintype "passive"))
      (node (ref "HD") (pin "G2") (pinfunction "GND_G2") (pintype "passive"))
      (node (ref "HD") (pin "G3") (pinfunction "GND_G3") (pintype "passive"))
      (node (ref "HD") (pin "G4") (pinfunction "GND_G4") (pintype "passive"))
      (node (ref "R4") (pin "2") (pintype "passive"))
    )
    (net (code "97") (name "Net-(HD-HPD)") (class "Default")
      (node (ref "HD") (pin "19") (pinfunction "HPD_19") (pintype "passive"))
      (node (ref "R1") (pin "2") (pintype "passive"))
    )
    (net (code "98") (name "Net-(R1-Pad1)") (class "Default")
      (node (ref "R1") (pin "1") (pintype "passive"))
      (node (ref "R2") (pin "1") (pintype "passive"))
      (node (ref "R3") (pin "1") (pintype "passive"))
      (node (ref "R5") (pin "1") (pintype "passive"))
    )
    (net (code "99") (name "Net-(TFT_RGB-B0)") (class "Default")
      (node (ref "RP2") (pin "8") (pintype "passive"))
      (node (ref "TFT_RGB") (pin "19") (pinfunction "B0_19") (pintype "passive"))
    )
    (net (code "100") (name "Net-(TFT_RGB-B1)") (class "Default")
      (node (ref "RP2") (pin "6") (pintype "passive"))
      (node (ref "TFT_RGB") (pin "18") (pinfunction "B1_18") (pintype "passive"))
    )
    (net (code "101") (name "Net-(TFT_RGB-B2)") (class "Default")
      (node (ref "RP2") (pin "4") (pintype "passive"))
      (node (ref "TFT_RGB") (pin "17") (pinfunction "B2_17") (pintype "passive"))
    )
    (net (code "102") (name "Net-(TFT_RGB-B3)") (class "Default")
      (node (ref "RP2") (pin "2") (pintype "passive"))
      (node (ref "TFT_RGB") (pin "16") (pinfunction "B3_16") (pintype "passive"))
    )
    (net (code "103") (name "Net-(TFT_RGB-B4)") (class "Default")
      (node (ref "RP1") (pin "8") (pintype "passive"))
      (node (ref "TFT_RGB") (pin "15") (pinfunction "B4_15") (pintype "passive"))
    )
    (net (code "104") (name "Net-(TFT_RGB-B5)") (class "Default")
      (node (ref "RP1") (pin "6") (pintype "passive"))
      (node (ref "TFT_RGB") (pin "14") (pinfunction "B5_14") (pintype "passive"))
    )
    (net (code "105") (name "Net-(TFT_RGB-B6)") (class "Default")
      (node (ref "RP1") (pin "4") (pintype "passive"))
      (node (ref "TFT_RGB") (pin "13") (pinfunction "B6_13") (pintype "passive"))
    )
    (net (code "106") (name "Net-(TFT_RGB-B7)") (class "Default")
      (node (ref "RP1") (pin "2") (pintype "passive"))
      (node (ref "TFT_RGB") (pin "12") (pinfunction "B7_12") (pintype "passive"))
    )
    (net (code "107") (name "Net-(TFT_RGB-DCLK)") (class "Default")
      (node (ref "RP7") (pin "8") (pintype "passive"))
      (node (ref "TFT_RGB") (pin "37") (pinfunction "DCLK_37") (pintype "passive"))
    )
    (net (code "108") (name "Net-(TFT_RGB-DE)") (class "Default")
      (node (ref "RP7") (pin "2") (pintype "passive"))
      (node (ref "TFT_RGB") (pin "9") (pinfunction "DE_9") (pintype "passive"))
    )
    (net (code "109") (name "Net-(TFT_RGB-G0)") (class "Default")
      (node (ref "RP4") (pin "8") (pintype "passive"))
      (node (ref "TFT_RGB") (pin "27") (pinfunction "G0_27") (pintype "passive"))
    )
    (net (code "110") (name "Net-(TFT_RGB-G1)") (class "Default")
      (node (ref "RP4") (pin "6") (pintype "passive"))
      (node (ref "TFT_RGB") (pin "26") (pinfunction "G1_26") (pintype "passive"))
    )
    (net (code "111") (name "Net-(TFT_RGB-G2)") (class "Default")
      (node (ref "RP4") (pin "4") (pintype "passive"))
      (node (ref "TFT_RGB") (pin "25") (pinfunction "G2_25") (pintype "passive"))
    )
    (net (code "112") (name "Net-(TFT_RGB-G3)") (class "Default")
      (node (ref "RP4") (pin "2") (pintype "passive"))
      (node (ref "TFT_RGB") (pin "24") (pinfunction "G3_24") (pintype "passive"))
    )
    (net (code "113") (name "Net-(TFT_RGB-G4)") (class "Default")
      (node (ref "RP3") (pin "8") (pintype "passive"))
      (node (ref "TFT_RGB") (pin "23") (pinfunction "G4_23") (pintype "passive"))
    )
    (net (code "114") (name "Net-(TFT_RGB-G5)") (class "Default")
      (node (ref "RP3") (pin "6") (pintype "passive"))
      (node (ref "TFT_RGB") (pin "22") (pinfunction "G5_22") (pintype "passive"))
    )
    (net (code "115") (name "Net-(TFT_RGB-G6)") (class "Default")
      (node (ref "RP3") (pin "4") (pintype "passive"))
      (node (ref "TFT_RGB") (pin "21") (pinfunction "G6_21") (pintype "passive"))
    )
    (net (code "116") (name "Net-(TFT_RGB-G7)") (class "Default")
      (node (ref "RP3") (pin "2") (pintype "passive"))
      (node (ref "TFT_RGB") (pin "20") (pinfunction "G7_20") (pintype "passive"))
    )
    (net (code "117") (name "Net-(TFT_RGB-HS)") (class "Default")
      (node (ref "RP7") (pin "6") (pintype "passive"))
      (node (ref "TFT_RGB") (pin "11") (pinfunction "HS_11") (pintype "passive"))
    )
    (net (code "118") (name "Net-(TFT_RGB-MODE)") (class "Default")
      (node (ref "R16") (pin "2") (pintype "passive"))
      (node (ref "TFT_RGB") (pin "8") (pinfunction "MODE_8") (pintype "passive"))
    )
    (net (code "119") (name "Net-(TFT_RGB-R0)") (class "Default")
      (node (ref "RP6") (pin "8") (pintype "passive"))
      (node (ref "TFT_RGB") (pin "35") (pinfunction "R0_35") (pintype "passive"))
    )
    (net (code "120") (name "Net-(TFT_RGB-R1)") (class "Default")
      (node (ref "RP6") (pin "6") (pintype "passive"))
      (node (ref "TFT_RGB") (pin "34") (pinfunction "R1_34") (pintype "passive"))
    )
    (net (code "121") (name "Net-(TFT_RGB-R2)") (class "Default")
      (node (ref "RP6") (pin "4") (pintype "passive"))
      (node (ref "TFT_RGB") (pin "33") (pinfunction "R2_33") (pintype "passive"))
    )
    (net (code "122") (name "Net-(TFT_RGB-R3)") (class "Default")
      (node (ref "RP6") (pin "2") (pintype "passive"))
      (node (ref "TFT_RGB") (pin "32") (pinfunction "R3_32") (pintype "passive"))
    )
    (net (code "123") (name "Net-(TFT_RGB-R4)") (class "Default")
      (node (ref "RP5") (pin "8") (pintype "passive"))
      (node (ref "TFT_RGB") (pin "31") (pinfunction "R4_31") (pintype "passive"))
    )
    (net (code "124") (name "Net-(TFT_RGB-R5)") (class "Default")
      (node (ref "RP5") (pin "6") (pintype "passive"))
      (node (ref "TFT_RGB") (pin "30") (pinfunction "R5_30") (pintype "passive"))
    )
    (net (code "125") (name "Net-(TFT_RGB-R6)") (class "Default")
      (node (ref "RP5") (pin "4") (pintype "passive"))
      (node (ref "TFT_RGB") (pin "29") (pinfunction "R6_29") (pintype "passive"))
    )
    (net (code "126") (name "Net-(TFT_RGB-R7)") (class "Default")
      (node (ref "RP5") (pin "2") (pintype "passive"))
      (node (ref "TFT_RGB") (pin "28") (pinfunction "R7_28") (pintype "passive"))
    )
    (net (code "127") (name "Net-(TFT_RGB-RESET)") (class "Default")
      (node (ref "R19") (pin "1") (pintype "passive"))
      (node (ref "TFT_RGB") (pin "44") (pinfunction "RESET_44") (pintype "passive"))
    )
    (net (code "128") (name "Net-(TFT_RGB-VS)") (class "Default")
      (node (ref "RP7") (pin "4") (pintype "passive"))
      (node (ref "TFT_RGB") (pin "10") (pinfunction "VS_10") (pintype "passive"))
    )
    (net (code "129") (name "Net-(U2-SW)") (class "Default")
      (node (ref "D1") (pin "1") (pintype "passive"))
      (node (ref "L1") (pin "2") (pintype "passive"))
      (node (ref "U2") (pin "1") (pinfunction "SW_1") (pintype "passive"))
    )
    (net (code "130") (name "Net-(U3-EN)") (class "Default")
      (node (ref "R28") (pin "1") (pintype "passive"))
      (node (ref "U3") (pin "8") (pinfunction "EN_8") (pintype "passive"))
    )
    (net (code "131") (name "Net-(U3-FB)") (class "Default")
      (node (ref "R29") (pin "2") (pintype "passive"))
      (node (ref "R30") (pin "1") (pintype "passive"))
      (node (ref "U3") (pin "7") (pinfunction "FB_7") (pintype "passive"))
    )
    (net (code "132") (name "Net-(U3-SW)") (class "Default")
      (node (ref "L3") (pin "2") (pintype "passive"))
      (node (ref "U3") (pin "3") (pinfunction "SW_3") (pintype "passive"))
    )
    (net (code "133") (name "Net-(U5-FB)") (class "Default")
      (node (ref "C32") (pin "2") (pintype "passive"))
      (node (ref "R31") (pin "2") (pintype "passive"))
      (node (ref "R32") (pin "2") (pintype "passive"))
      (node (ref "U5") (pin "3") (pinfunction "FB_3") (pintype "passive"))
    )
    (net (code "134") (name "Net-(U5-SW)") (class "Default")
      (node (ref "C25") (pin "2") (pintype "passive"))
      (node (ref "C26") (pin "1") (pintype "passive"))
      (node (ref "D5") (pin "1") (pintype "passive"))
      (node (ref "L5") (pin "1") (pinfunction "1_1") (pintype "passive"))
      (node (ref "U5") (pin "1") (pinfunction "SW_1") (pintype "passive"))
    )
    (net (code "135") (name "VCC-7") (class "Default")
      (node (ref "C23") (pin "1") (pintype "passive"))
      (node (ref "D6") (pin "2") (pintype "passive"))
      (node (ref "TFT_RGB") (pin "42") (pinfunction "VGL_42") (pintype "passive"))
    )
    (net (code "136") (name "VCC3.3") (class "Default")
      (node (ref "C10") (pin "2") (pintype "passive"))
      (node (ref "C11") (pin "2") (pintype "passive"))
      (node (ref "C16") (pin "2") (pintype "passive"))
      (node (ref "C2") (pin "2") (pintype "passive"))
      (node (ref "C21") (pin "2") (pintype "passive"))
      (node (ref "C22") (pin "2") (pintype "passive"))
      (node (ref "C3") (pin "2") (pintype "passive"))
      (node (ref "C38") (pin "2") (pintype "passive"))
      (node (ref "C39") (pin "2") (pintype "passive"))
      (node (ref "C4") (pin "2") (pintype "passive"))
      (node (ref "C40") (pin "2") (pintype "passive"))
      (node (ref "C41") (pin "2") (pintype "passive"))
      (node (ref "C42") (pin "2") (pintype "passive"))
      (node (ref "C5") (pin "2") (pintype "passive"))
      (node (ref "C6") (pin "2") (pintype "passive"))
      (node (ref "C7") (pin "2") (pintype "passive"))
      (node (ref "C8") (pin "2") (pintype "passive"))
      (node (ref "C9") (pin "2") (pintype "passive"))
      (node (ref "DBG") (pin "3") (pinfunction "3_3") (pintype "passive"))
      (node (ref "L3") (pin "1") (pintype "passive"))
      (node (ref "R10") (pin "1") (pintype "passive"))
      (node (ref "R11") (pin "1") (pintype "passive"))
      (node (ref "R12") (pin "1") (pintype "passive"))
      (node (ref "R13") (pin "1") (pintype "passive"))
      (node (ref "R14") (pin "1") (pintype "passive"))
      (node (ref "R16") (pin "1") (pintype "passive"))
      (node (ref "R19") (pin "2") (pintype "passive"))
      (node (ref "R20") (pin "1") (pintype "passive"))
      (node (ref "R22") (pin "1") (pintype "passive"))
      (node (ref "R27") (pin "2") (pintype "passive"))
      (node (ref "R29") (pin "1") (pintype "passive"))
      (node (ref "R34") (pin "2") (pintype "passive"))
      (node (ref "R37") (pin "2") (pinfunction "2_2") (pintype "passive"))
      (node (ref "R9") (pin "1") (pintype "passive"))
      (node (ref "TFT_RGB") (pin "7") (pinfunction "DVDD_7") (pintype "passive"))
      (node (ref "U1") (pin "18") (pinfunction "OVDD_18") (pintype "passive"))
      (node (ref "U1") (pin "29") (pinfunction "OVDD_29") (pintype "passive"))
      (node (ref "U1") (pin "38") (pinfunction "DVDD_38") (pintype "passive"))
      (node (ref "U1") (pin "43") (pinfunction "OVDD_43") (pintype "passive"))
      (node (ref "U1") (pin "57") (pinfunction "OVDD_57") (pintype "passive"))
      (node (ref "U1") (pin "6") (pinfunction "DVDD_6") (pintype "passive"))
      (node (ref "U1") (pin "67") (pinfunction "DVDD_67") (pintype "passive"))
      (node (ref "U1") (pin "78") (pinfunction "OVDD_78") (pintype "passive"))
      (node (ref "U1") (pin "82") (pinfunction "AVDD_82") (pintype "passive"))
      (node (ref "U1") (pin "84") (pinfunction "AVDD_84") (pintype "passive"))
      (node (ref "U1") (pin "88") (pinfunction "AVDD_88") (pintype "passive"))
      (node (ref "U1") (pin "95") (pinfunction "AVDD_95") (pintype "passive"))
      (node (ref "U1") (pin "97") (pinfunction "PVDD_97") (pintype "passive"))
      (node (ref "U1") (pin "99") (pinfunction "RSVD_99") (pintype "passive"))
      (node (ref "U3") (pin "5") (pinfunction "OUT_5") (pintype "passive"))
      (node (ref "U6") (pin "1") (pinfunction "VBAT_1") (pintype "passive"))
      (node (ref "U6") (pin "24") (pinfunction "VDD_1_24") (pintype "passive"))
      (node (ref "U6") (pin "36") (pinfunction "VDD_2_36") (pintype "passive"))
      (node (ref "U6") (pin "48") (pinfunction "VDD_3_48") (pintype "passive"))
      (node (ref "U6") (pin "9") (pinfunction "VDDA_9") (pintype "passive"))
    )
    (net (code "137") (name "VCC5") (class "Default")
      (node (ref "C17") (pin "2") (pintype "passive"))
      (node (ref "C19") (pin "2") (pintype "passive"))
      (node (ref "C20") (pin "2") (pintype "passive"))
      (node (ref "C29") (pin "2") (pintype "passive"))
      (node (ref "L1") (pin "1") (pintype "passive"))
      (node (ref "L5") (pin "2") (pinfunction "2_2") (pintype "passive"))
      (node (ref "PSW") (pin "2") (pinfunction "TP2_2") (pintype "passive"))
      (node (ref "PSW") (pin "3") (pinfunction "TP3_3") (pintype "passive"))
      (node (ref "R28") (pin "2") (pintype "passive"))
      (node (ref "RGB") (pin "1") (pinfunction "1_1") (pintype "passive"))
      (node (ref "RGB") (pin "2") (pinfunction "2_2") (pintype "passive"))
      (node (ref "U2") (pin "5") (pinfunction "IN_5") (pintype "passive"))
      (node (ref "U3") (pin "2") (pinfunction "VIN_2") (pintype "passive"))
      (node (ref "U5") (pin "4") (pinfunction "EN_4") (pintype "passive"))
      (node (ref "U5") (pin "5") (pinfunction "VIN_5") (pintype "passive"))
      (node (ref "USB") (pin "11") (pinfunction "VBUS(B4+A9)_11") (pintype "passive"))
      (node (ref "USB") (pin "2") (pinfunction "VBUS(A4+B9)_2") (pintype "passive"))
    )
    (net (code "138") (name "VCC10.4") (class "Default")
      (node (ref "C27") (pin "1") (pintype "passive"))
      (node (ref "C30") (pin "2") (pintype "passive"))
      (node (ref "C31") (pin "1") (pintype "passive"))
      (node (ref "C32") (pin "1") (pintype "passive"))
      (node (ref "D5") (pin "2") (pintype "passive"))
      (node (ref "D9") (pin "1") (pintype "passive"))
      (node (ref "R17") (pin "2") (pintype "passive"))
      (node (ref "R31") (pin "1") (pintype "passive"))
      (node (ref "TFT_RGB") (pin "43") (pinfunction "AVDD_43") (pintype "passive"))
    )
    (net (code "139") (name "VCC16") (class "Default")
      (node (ref "C28") (pin "2") (pintype "passive"))
      (node (ref "D7") (pin "1") (pintype "passive"))
      (node (ref "TFT_RGB") (pin "41") (pinfunction "VGH_41") (pintype "passive"))
    )
    (net (code "140") (name "unconnected-(HD-CEC-Pad13)") (class "Default")
      (node (ref "HD") (pin "13") (pinfunction "CEC_13") (pintype "passive"))
    )
    (net (code "141") (name "unconnected-(HD-Utility-Pad14)") (class "Default")
      (node (ref "HD") (pin "14") (pinfunction "Utility_14") (pintype "passive"))
    )
    (net (code "142") (name "unconnected-(RGB-PadA)") (class "Default")
      (node (ref "RGB") (pin "A") (pinfunction "A_A") (pintype "passive"))
    )
    (net (code "143") (name "unconnected-(RGB-PadB)") (class "Default")
      (node (ref "RGB") (pin "B") (pinfunction "B_B") (pintype "passive"))
    )
    (net (code "144") (name "unconnected-(TFT_RGB-NC-Pad45)") (class "Default")
      (node (ref "TFT_RGB") (pin "45") (pinfunction "NC_45") (pintype "passive"))
    )
    (net (code "145") (name "unconnected-(TFT_RGB-NC-Pad49)") (class "Default")
      (node (ref "TFT_RGB") (pin "49") (pinfunction "NC_49") (pintype "passive"))
    )
    (net (code "146") (name "unconnected-(TFT_RGB-NC-Pad50)") (class "Default")
      (node (ref "TFT_RGB") (pin "50") (pinfunction "NC_50") (pintype "passive"))
    )
    (net (code "147") (name "unconnected-(U1-CTL1-Pad40)") (class "Default")
      (node (ref "U1") (pin "40") (pinfunction "CTL1_40") (pintype "passive"))
    )
    (net (code "148") (name "unconnected-(U1-CTL2-Pad41)") (class "Default")
      (node (ref "U1") (pin "41") (pinfunction "CTL2_41") (pintype "passive"))
    )
    (net (code "149") (name "unconnected-(U1-CTL3-Pad42)") (class "Default")
      (node (ref "U1") (pin "42") (pinfunction "CTL3_42") (pintype "passive"))
    )
    (net (code "150") (name "unconnected-(U1-EXT_RES-Pad96)") (class "Default")
      (node (ref "U1") (pin "96") (pinfunction "EXT_RES_96") (pintype "passive"))
    )
    (net (code "151") (name "unconnected-(U1-QO0-Pad49)") (class "Default")
      (node (ref "U1") (pin "49") (pinfunction "QO0_49") (pintype "passive"))
    )
    (net (code "152") (name "unconnected-(U1-QO1-Pad50)") (class "Default")
      (node (ref "U1") (pin "50") (pinfunction "QO1_50") (pintype "passive"))
    )
    (net (code "153") (name "unconnected-(U1-QO2-Pad51)") (class "Default")
      (node (ref "U1") (pin "51") (pinfunction "QO2_51") (pintype "passive"))
    )
    (net (code "154") (name "unconnected-(U1-QO3-Pad52)") (class "Default")
      (node (ref "U1") (pin "52") (pinfunction "QO3_52") (pintype "passive"))
    )
    (net (code "155") (name "unconnected-(U1-QO4-Pad53)") (class "Default")
      (node (ref "U1") (pin "53") (pinfunction "QO4_53") (pintype "passive"))
    )
    (net (code "156") (name "unconnected-(U1-QO5-Pad54)") (class "Default")
      (node (ref "U1") (pin "54") (pinfunction "QO5_54") (pintype "passive"))
    )
    (net (code "157") (name "unconnected-(U1-QO6-Pad55)") (class "Default")
      (node (ref "U1") (pin "55") (pinfunction "QO6_55") (pintype "passive"))
    )
    (net (code "158") (name "unconnected-(U1-QO7-Pad56)") (class "Default")
      (node (ref "U1") (pin "56") (pinfunction "QO7_56") (pintype "passive"))
    )
    (net (code "159") (name "unconnected-(U1-QO8-Pad59)") (class "Default")
      (node (ref "U1") (pin "59") (pinfunction "QO8_59") (pintype "passive"))
    )
    (net (code "160") (name "unconnected-(U1-QO9-Pad60)") (class "Default")
      (node (ref "U1") (pin "60") (pinfunction "QO9_60") (pintype "passive"))
    )
    (net (code "161") (name "unconnected-(U1-QO10-Pad61)") (class "Default")
      (node (ref "U1") (pin "61") (pinfunction "QO10_61") (pintype "passive"))
    )
    (net (code "162") (name "unconnected-(U1-QO11-Pad62)") (class "Default")
      (node (ref "U1") (pin "62") (pinfunction "QO11_62") (pintype "passive"))
    )
    (net (code "163") (name "unconnected-(U1-QO12-Pad63)") (class "Default")
      (node (ref "U1") (pin "63") (pinfunction "QO12_63") (pintype "passive"))
    )
    (net (code "164") (name "unconnected-(U1-QO13-Pad64)") (class "Default")
      (node (ref "U1") (pin "64") (pinfunction "QO13_64") (pintype "passive"))
    )
    (net (code "165") (name "unconnected-(U1-QO14-Pad65)") (class "Default")
      (node (ref "U1") (pin "65") (pinfunction "QO14_65") (pintype "passive"))
    )
    (net (code "166") (name "unconnected-(U1-QO15-Pad66)") (class "Default")
      (node (ref "U1") (pin "66") (pinfunction "QO15_66") (pintype "passive"))
    )
    (net (code "167") (name "unconnected-(U1-QO16-Pad69)") (class "Default")
      (node (ref "U1") (pin "69") (pinfunction "QO16_69") (pintype "passive"))
    )
    (net (code "168") (name "unconnected-(U1-QO17-Pad70)") (class "Default")
      (node (ref "U1") (pin "70") (pinfunction "QO17_70") (pintype "passive"))
    )
    (net (code "169") (name "unconnected-(U1-QO18-Pad71)") (class "Default")
      (node (ref "U1") (pin "71") (pinfunction "QO18_71") (pintype "passive"))
    )
    (net (code "170") (name "unconnected-(U1-QO19-Pad72)") (class "Default")
      (node (ref "U1") (pin "72") (pinfunction "QO19_72") (pintype "passive"))
    )
    (net (code "171") (name "unconnected-(U1-QO20-Pad73)") (class "Default")
      (node (ref "U1") (pin "73") (pinfunction "QO20_73") (pintype "passive"))
    )
    (net (code "172") (name "unconnected-(U1-QO21-Pad74)") (class "Default")
      (node (ref "U1") (pin "74") (pinfunction "QO21_74") (pintype "passive"))
    )
    (net (code "173") (name "unconnected-(U1-QO22-Pad75)") (class "Default")
      (node (ref "U1") (pin "75") (pinfunction "QO22_75") (pintype "passive"))
    )
    (net (code "174") (name "unconnected-(U1-QO23-Pad77)") (class "Default")
      (node (ref "U1") (pin "77") (pinfunction "QO23_77") (pintype "passive"))
    )
    (net (code "175") (name "unconnected-(U3-PG-Pad1)") (class "Default")
      (node (ref "U3") (pin "1") (pinfunction "PG_1") (pintype "passive"))
    )
    (net (code "176") (name "unconnected-(USB-CC1(A5)-Pad4)") (class "Default")
      (node (ref "USB") (pin "4") (pinfunction "CC1(A5)_4") (pintype "passive+no_connect"))
    )
    (net (code "177") (name "unconnected-(USB-CC2(B5)-Pad10)") (class "Default")
      (node (ref "USB") (pin "10") (pinfunction "CC2(B5)_10") (pintype "passive+no_connect"))
    )
    (net (code "178") (name "unconnected-(USB-SBU1(A8)-Pad9)") (class "Default")
      (node (ref "USB") (pin "9") (pinfunction "SBU1(A8)_9") (pintype "passive+no_connect"))
    )
    (net (code "179") (name "unconnected-(USB-SBU2(B8)-Pad3)") (class "Default")
      (node (ref "USB") (pin "3") (pinfunction "SBU2(B8)_3") (pintype "passive+no_connect"))
    )
  )
)
